# Frisbie_Board.net
KiCad netlist of a schematic drawn in EAGLE
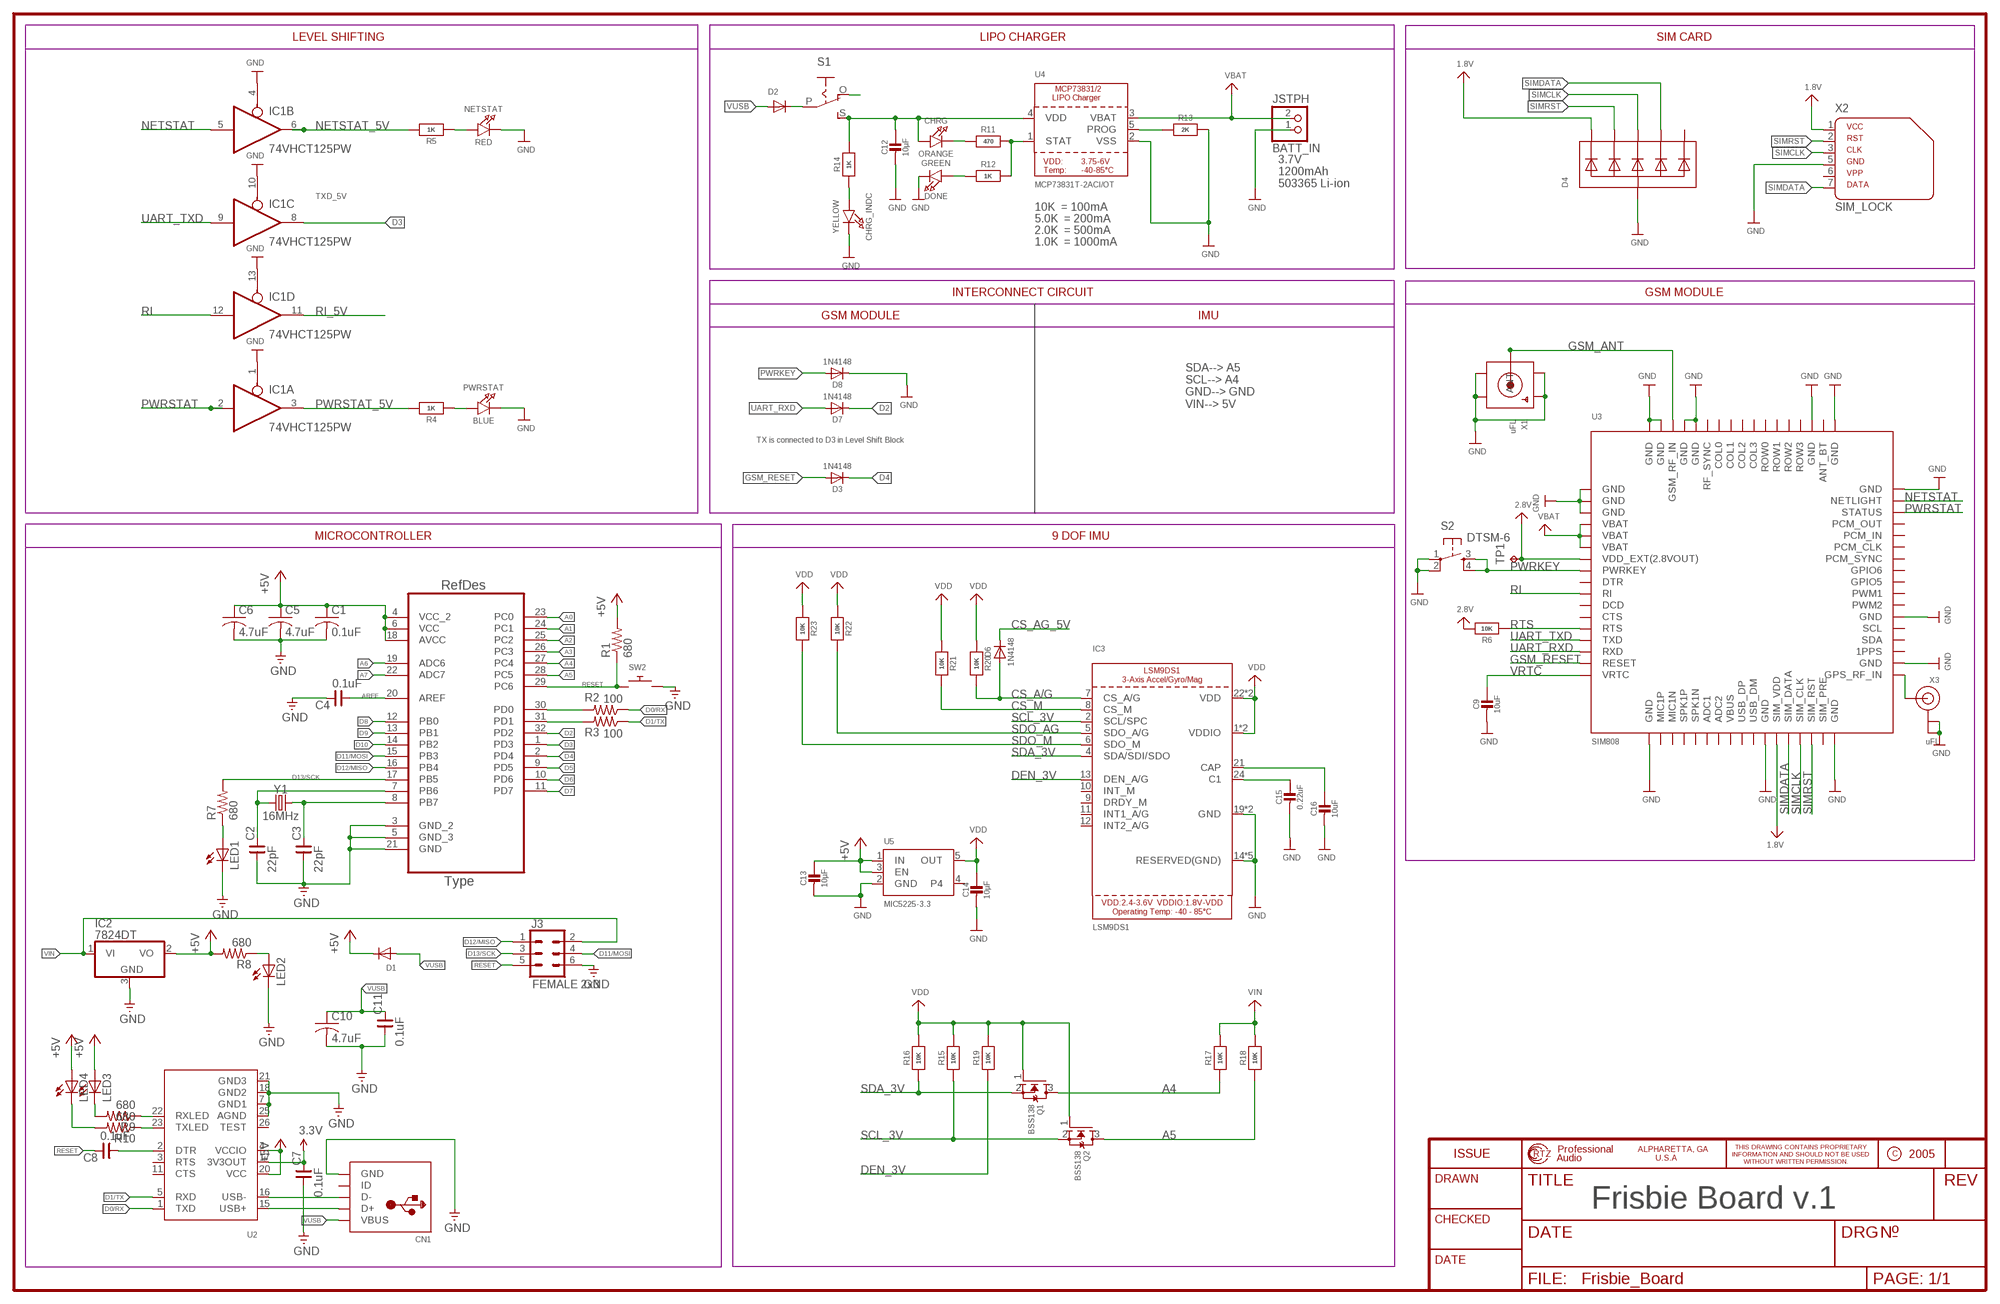
[diagram p0: schematic, sheet 1]

(export (version "E")
  (design (tool "Eeschema 10.0.6"))
  (components
    (comp (ref "BATT_IN")
      (value "JSTPH")
      (footprint "eagle-import:JSTPH2")
      (libsource (lib "eagle-import") (part "JST_2PIN"))
    )
    (comp (ref "C1")
      (value "0.1uF")
      (footprint "eagle-import:C0805")
      (libsource (lib "eagle-import") (part "C-USC0805"))
    )
    (comp (ref "C2")
      (value "22pF")
      (footprint "eagle-import:0805")
      (libsource (lib "eagle-import") (part "CNP-0805"))
    )
    (comp (ref "C3")
      (value "22pF")
      (footprint "eagle-import:0805")
      (libsource (lib "eagle-import") (part "CNP-0805"))
    )
    (comp (ref "C4")
      (value "0.1uF")
      (footprint "eagle-import:0805")
      (libsource (lib "eagle-import") (part "CNP-0805"))
    )
    (comp (ref "C5")
      (value "4.7uF")
      (footprint "eagle-import:C0805")
      (libsource (lib "eagle-import") (part "C-USC0805"))
    )
    (comp (ref "C6")
      (value "4.7uF")
      (footprint "eagle-import:C0805")
      (libsource (lib "eagle-import") (part "C-USC0805"))
    )
    (comp (ref "C7")
      (value "0.1uF")
      (footprint "eagle-import:0805")
      (libsource (lib "eagle-import") (part "CNP-0805"))
    )
    (comp (ref "C8")
      (value "0.1uF")
      (footprint "eagle-import:0805")
      (libsource (lib "eagle-import") (part "CNP-0805"))
    )
    (comp (ref "C9")
      (value "10uF")
      (footprint "eagle-import:0805-NO")
      (libsource (lib "eagle-import") (part "CAP_CERAMIC0805-NOOUTLINE"))
    )
    (comp (ref "C10")
      (value "4.7uF")
      (footprint "eagle-import:C0805")
      (libsource (lib "eagle-import") (part "C-USC0805"))
    )
    (comp (ref "C11")
      (value "0.1uF")
      (footprint "eagle-import:0805")
      (libsource (lib "eagle-import") (part "CNP-0805"))
    )
    (comp (ref "C12")
      (value "10µF")
      (footprint "eagle-import:0805-NO")
      (libsource (lib "eagle-import") (part "CAP_CERAMIC0805-NOOUTLINE"))
    )
    (comp (ref "C13")
      (value "10µF")
      (footprint "eagle-import:0805-NO")
      (libsource (lib "eagle-import") (part "CAP_CERAMIC0805-NOOUTLINE"))
    )
    (comp (ref "C14")
      (value "10µF")
      (footprint "eagle-import:0805-NO")
      (libsource (lib "eagle-import") (part "CAP_CERAMIC0805-NOOUTLINE"))
    )
    (comp (ref "C15")
      (value "0.22uF")
      (footprint "eagle-import:0805_10MGAP")
      (libsource (lib "eagle-import") (part "CAP_CERAMIC0805_10MGAP"))
    )
    (comp (ref "C16")
      (value "10uF")
      (footprint "eagle-import:0805-NO")
      (libsource (lib "eagle-import") (part "CAP_CERAMIC0805-NOOUTLINE"))
    )
    (comp (ref "CHRG")
      (value "ORANGE")
      (footprint "eagle-import:CHIPLED_0805_NOOUTLINE")
      (libsource (lib "eagle-import") (part "LED0805_NOOUTLINE"))
    )
    (comp (ref "CHRG_INDC")
      (value "YELLOW")
      (footprint "eagle-import:CHIPLED_0805_NOOUTLINE")
      (libsource (lib "eagle-import") (part "LED0805_NOOUTLINE"))
    )
    (comp (ref "CN1")
      (value "USBMINIB")
      (footprint "eagle-import:USB-MINIB")
      (libsource (lib "eagle-import") (part "USBMINIB"))
    )
    (comp (ref "D1")
      (value "DIODESOD-123")
      (footprint "eagle-import:SOD-123")
      (libsource (lib "eagle-import") (part "DIODESOD-123"))
    )
    (comp (ref "D2")
      (value "DIODESOD-123")
      (footprint "eagle-import:SOD-123")
      (libsource (lib "eagle-import") (part "DIODESOD-123"))
    )
    (comp (ref "D3")
      (value "1N4148")
      (footprint "eagle-import:SOD-323")
      (libsource (lib "eagle-import") (part "DIODESOD-323"))
    )
    (comp (ref "D4")
      (value "TVSARRAY_5LANE")
      (footprint "eagle-import:SOT363")
      (libsource (lib "eagle-import") (part "TVSARRAY_5LANE"))
    )
    (comp (ref "D6")
      (value "1N4148")
      (footprint "eagle-import:SOD-323")
      (libsource (lib "eagle-import") (part "DIODESOD-323"))
    )
    (comp (ref "D7")
      (value "1N4148")
      (footprint "eagle-import:SOD-323")
      (libsource (lib "eagle-import") (part "DIODESOD-323"))
    )
    (comp (ref "D8")
      (value "1N4148")
      (footprint "eagle-import:SOD-323")
      (libsource (lib "eagle-import") (part "DIODESOD-323"))
    )
    (comp (ref "DONE")
      (value "GREEN")
      (footprint "eagle-import:CHIPLED_0805_NOOUTLINE")
      (libsource (lib "eagle-import") (part "LED0805_NOOUTLINE"))
    )
    (comp (ref "IC1")
      (value "74VHCT125PW")
      (footprint "eagle-import:TSSOP14")
      (libsource (lib "eagle-import") (part "74125PWABT"))
    )
    (comp (ref "IC2")
      (value "7824DT")
      (footprint "eagle-import:TO252")
      (libsource (lib "eagle-import") (part "78DT24"))
    )
    (comp (ref "IC3")
      (value "LSM9DS1")
      (footprint "eagle-import:LGA24_3.5X3.1MM")
      (libsource (lib "eagle-import") (part "LSM9DS1"))
    )
    (comp (ref "J3")
      (value "FEMALE 2x3")
      (footprint "eagle-import:2X3")
      (libsource (lib "eagle-import") (part "CONN_03X2FEMALE"))
    )
    (comp (ref "LED1")
      (value "LEDCHIPLED_0805")
      (footprint "eagle-import:CHIPLED_0805")
      (libsource (lib "eagle-import") (part "LEDCHIPLED_0805"))
    )
    (comp (ref "LED2")
      (value "LEDCHIPLED_0805")
      (footprint "eagle-import:CHIPLED_0805")
      (libsource (lib "eagle-import") (part "LEDCHIPLED_0805"))
    )
    (comp (ref "LED3")
      (value "LEDCHIPLED_0805")
      (footprint "eagle-import:CHIPLED_0805")
      (libsource (lib "eagle-import") (part "LEDCHIPLED_0805"))
    )
    (comp (ref "LED4")
      (value "LEDCHIPLED_0805")
      (footprint "eagle-import:CHIPLED_0805")
      (libsource (lib "eagle-import") (part "LEDCHIPLED_0805"))
    )
    (comp (ref "NETSTAT")
      (value "RED")
      (footprint "eagle-import:CHIPLED_0805_NOOUTLINE")
      (libsource (lib "eagle-import") (part "LED0805_NOOUTLINE"))
    )
    (comp (ref "PWRSTAT")
      (value "BLUE")
      (footprint "eagle-import:CHIPLED_0805_NOOUTLINE")
      (libsource (lib "eagle-import") (part "LED0805_NOOUTLINE"))
    )
    (comp (ref "Q1")
      (value "BSS138")
      (footprint "eagle-import:SOT23-WIDE")
      (libsource (lib "eagle-import") (part "MOSFET-NWIDE"))
    )
    (comp (ref "Q2")
      (value "BSS138")
      (footprint "eagle-import:SOT23-WIDE")
      (libsource (lib "eagle-import") (part "MOSFET-NWIDE"))
    )
    (comp (ref "R1")
      (value "680")
      (footprint "eagle-import:R0805")
      (libsource (lib "eagle-import") (part "R-US_R0805"))
    )
    (comp (ref "R2")
      (value "100")
      (footprint "eagle-import:R0805")
      (libsource (lib "eagle-import") (part "R-US_R0805"))
    )
    (comp (ref "R3")
      (value "100")
      (footprint "eagle-import:R0805")
      (libsource (lib "eagle-import") (part "R-US_R0805"))
    )
    (comp (ref "R4")
      (value "1K")
      (footprint "eagle-import:0805-NO")
      (libsource (lib "eagle-import") (part "RESISTOR0805_NOOUTLINE"))
    )
    (comp (ref "R5")
      (value "1K")
      (footprint "eagle-import:0805-NO")
      (libsource (lib "eagle-import") (part "RESISTOR0805_NOOUTLINE"))
    )
    (comp (ref "R6")
      (value "10K")
      (footprint "eagle-import:0805-NO")
      (libsource (lib "eagle-import") (part "RESISTOR0805_NOOUTLINE"))
    )
    (comp (ref "R7")
      (value "680")
      (footprint "eagle-import:R0805")
      (libsource (lib "eagle-import") (part "R-US_R0805"))
    )
    (comp (ref "R8")
      (value "680")
      (footprint "eagle-import:R0805")
      (libsource (lib "eagle-import") (part "R-US_R0805"))
    )
    (comp (ref "R9")
      (value "680")
      (footprint "eagle-import:R0805")
      (libsource (lib "eagle-import") (part "R-US_R0805"))
    )
    (comp (ref "R10")
      (value "680")
      (footprint "eagle-import:R0805")
      (libsource (lib "eagle-import") (part "R-US_R0805"))
    )
    (comp (ref "R11")
      (value "470")
      (footprint "eagle-import:0805-NO")
      (libsource (lib "eagle-import") (part "RESISTOR0805_NOOUTLINE"))
    )
    (comp (ref "R12")
      (value "1K")
      (footprint "eagle-import:0805-NO")
      (libsource (lib "eagle-import") (part "RESISTOR0805_NOOUTLINE"))
    )
    (comp (ref "R13")
      (value "2K")
      (footprint "eagle-import:0805-NO")
      (libsource (lib "eagle-import") (part "RESISTOR0805_NOOUTLINE"))
    )
    (comp (ref "R14")
      (value "1K")
      (footprint "eagle-import:0805-NO")
      (libsource (lib "eagle-import") (part "RESISTOR0805_NOOUTLINE"))
    )
    (comp (ref "R15")
      (value "10K")
      (footprint "eagle-import:0805-NO")
      (libsource (lib "eagle-import") (part "RESISTOR0805_NOOUTLINE"))
    )
    (comp (ref "R16")
      (value "10K")
      (footprint "eagle-import:0805_10MGAP")
      (libsource (lib "eagle-import") (part "RESISTOR0805_10MGAP"))
    )
    (comp (ref "R17")
      (value "10K")
      (footprint "eagle-import:0805-NO")
      (libsource (lib "eagle-import") (part "RESISTOR0805_NOOUTLINE"))
    )
    (comp (ref "R18")
      (value "10K")
      (footprint "eagle-import:0805-NO")
      (libsource (lib "eagle-import") (part "RESISTOR0805_NOOUTLINE"))
    )
    (comp (ref "R19")
      (value "10K")
      (footprint "eagle-import:0805-NO")
      (libsource (lib "eagle-import") (part "RESISTOR0805_NOOUTLINE"))
    )
    (comp (ref "R20")
      (value "10K")
      (footprint "eagle-import:0805-NO")
      (libsource (lib "eagle-import") (part "RESISTOR0805_NOOUTLINE"))
    )
    (comp (ref "R21")
      (value "10K")
      (footprint "eagle-import:0805-NO")
      (libsource (lib "eagle-import") (part "RESISTOR0805_NOOUTLINE"))
    )
    (comp (ref "R22")
      (value "10K")
      (footprint "eagle-import:0805_10MGAP")
      (libsource (lib "eagle-import") (part "RESISTOR0805_10MGAP"))
    )
    (comp (ref "R23")
      (value "10K")
      (footprint "eagle-import:0805-NO")
      (libsource (lib "eagle-import") (part "RESISTOR0805_NOOUTLINE"))
    )
    (comp (ref "S1")
      (value "EG1218S")
      (footprint "eagle-import:EG1218")
      (libsource (lib "eagle-import") (part "EG1218S"))
    )
    (comp (ref "S2")
      (value "DTSM-6")
      (footprint "eagle-import:DTSM-6")
      (libsource (lib "eagle-import") (part "DTSM-6"))
    )
    (comp (ref "SW2")
      (value "SWITCH_PUSHBUTTONEVQ-PE")
      (footprint "eagle-import:TACT_PANA-EVQ")
      (libsource (lib "eagle-import") (part "SWITCH_PUSHBUTTONEVQ-PE"))
    )
    (comp (ref "TP1")
      (value "TPTP11R")
      (footprint "eagle-import:TP11R")
      (libsource (lib "eagle-import") (part "TPTP11R"))
    )
    (comp (ref "U1")
      (value "ATMEGA328P-AU")
      (footprint "eagle-import:QFP80P900X900X120-32N")
      (libsource (lib "eagle-import") (part "ATMEGA328P-AU"))
    )
    (comp (ref "U2")
      (value "FT232RLSSOP28")
      (footprint "eagle-import:SSOP28DB")
      (libsource (lib "eagle-import") (part "FT232RLSSOP28"))
    )
    (comp (ref "U3")
      (value "SIM808")
      (footprint "eagle-import:SIM900_SMT")
      (libsource (lib "eagle-import") (part "GSM_SIM808_LITERAL"))
    )
    (comp (ref "U4")
      (value "MCP73831T-2ACI/OT")
      (footprint "eagle-import:SOT23-5")
      (libsource (lib "eagle-import") (part "MCP73831/2"))
    )
    (comp (ref "U5")
      (value "MIC5225-3.3")
      (footprint "eagle-import:SOT23-5")
      (libsource (lib "eagle-import") (part "VREG_SOT23-5"))
    )
    (comp (ref "X1")
      (value "uFL")
      (footprint "eagle-import:SMA_EDGELAUNCH_UFL")
      (libsource (lib "eagle-import") (part "SMACONNECTOR_EDGE_UFL"))
    )
    (comp (ref "X2")
      (value "SIM_LOCK")
      (footprint "eagle-import:SIM_5002")
      (libsource (lib "eagle-import") (part "SIM_LOCK"))
    )
    (comp (ref "X3")
      (value "uFL")
      (footprint "eagle-import:U.FL")
      (libsource (lib "eagle-import") (part "ANTENNA_U.FL"))
    )
    (comp (ref "Y1")
      (value "16MHz")
      (footprint "eagle-import:HC49US")
      (libsource (lib "eagle-import") (part "CRYSTAL-16MHZPTH-HC49US"))
    )
  )
  (nets
    (net (code "1") (name "+5V") (class "Default")
      (node (ref "C1") (pin "1") (pinfunction "1_1") (pintype "passive"))
      (node (ref "C13") (pin "1") (pinfunction "1_1") (pintype "passive"))
      (node (ref "C5") (pin "1") (pinfunction "1_1") (pintype "passive"))
      (node (ref "C6") (pin "1") (pinfunction "1_1") (pintype "passive"))
      (node (ref "D1") (pin "C") (pinfunction "C_C") (pintype "passive"))
      (node (ref "IC2") (pin "2") (pinfunction "VO_2") (pintype "passive"))
      (node (ref "LED3") (pin "A") (pinfunction "A_A") (pintype "passive"))
      (node (ref "LED4") (pin "A") (pinfunction "A_A") (pintype "passive"))
      (node (ref "R1") (pin "2") (pinfunction "2_2") (pintype "passive"))
      (node (ref "R8") (pin "2") (pinfunction "2_2") (pintype "passive"))
      (node (ref "U1") (pin "18") (pinfunction "AVCC_18") (pintype "power_in"))
      (node (ref "U1") (pin "4") (pinfunction "VCC_2_4") (pintype "power_in"))
      (node (ref "U1") (pin "6") (pinfunction "VCC_6") (pintype "power_in"))
      (node (ref "U2") (pin "20") (pinfunction "VCC_20") (pintype "power_in"))
      (node (ref "U2") (pin "4") (pinfunction "VCCIO_4") (pintype "power_in"))
      (node (ref "U5") (pin "1") (pinfunction "IN_1") (pintype "power_in"))
      (node (ref "U5") (pin "3") (pinfunction "EN_3") (pintype "input"))
    )
    (net (code "2") (name "/AREF") (class "Default")
      (node (ref "C4") (pin "1") (pinfunction "1_1") (pintype "passive"))
      (node (ref "U1") (pin "20") (pinfunction "AREF_20") (pintype "input"))
    )
    (net (code "3") (name "/CS_AG_5V") (class "Default")
      (node (ref "D6") (pin "C") (pinfunction "C_C") (pintype "passive"))
    )
    (net (code "4") (name "/CS_A{slash}G") (class "Default")
      (node (ref "D6") (pin "A") (pinfunction "A_A") (pintype "passive"))
      (node (ref "IC3") (pin "7") (pinfunction "CS_A/G_7") (pintype "bidirectional"))
      (node (ref "R20") (pin "2") (pinfunction "2_2") (pintype "passive"))
    )
    (net (code "5") (name "/CS_M") (class "Default")
      (node (ref "IC3") (pin "8") (pinfunction "CS_M_8") (pintype "bidirectional"))
      (node (ref "R21") (pin "2") (pinfunction "2_2") (pintype "passive"))
    )
    (net (code "6") (name "/DEN_3V") (class "Default")
      (node (ref "IC3") (pin "13") (pinfunction "DEN_A/G_13") (pintype "bidirectional"))
      (node (ref "R19") (pin "1") (pinfunction "1_1") (pintype "passive"))
    )
    (net (code "7") (name "/GSM_ANT") (class "Default")
      (node (ref "U3") (pin "P$66") (pinfunction "GSM_RF_IN_P$66") (pintype "input"))
      (node (ref "X1") (pin "P") (pinfunction "ANT_P") (pintype "bidirectional"))
    )
    (net (code "8") (name "/NETSTAT") (class "Default")
      (node (ref "IC1") (pin "5") (pinfunction "I_5") (pintype "input"))
      (node (ref "U3") (pin "P$50") (pinfunction "NETLIGHT_P$50") (pintype "output"))
    )
    (net (code "9") (name "/NETSTAT_5V") (class "Default")
      (node (ref "IC1") (pin "6") (pinfunction "O_6") (pintype "tri_state"))
      (node (ref "R5") (pin "2") (pinfunction "2_2") (pintype "passive"))
    )
    (net (code "10") (name "/PWRSTAT") (class "Default")
      (node (ref "IC1") (pin "2") (pinfunction "I_2") (pintype "input"))
      (node (ref "U3") (pin "P$49") (pinfunction "STATUS_P$49") (pintype "output"))
    )
    (net (code "11") (name "/PWRSTAT_5V") (class "Default")
      (node (ref "IC1") (pin "3") (pinfunction "O_3") (pintype "tri_state"))
      (node (ref "R4") (pin "2") (pinfunction "2_2") (pintype "passive"))
    )
    (net (code "12") (name "/RI") (class "Default")
      (node (ref "IC1") (pin "12") (pinfunction "I_12") (pintype "input"))
      (node (ref "U3") (pin "P$10") (pinfunction "RI_P$10") (pintype "output"))
    )
    (net (code "13") (name "/RI_5V") (class "Default")
      (node (ref "IC1") (pin "11") (pinfunction "O_11") (pintype "tri_state"))
    )
    (net (code "14") (name "/RTS") (class "Default")
      (node (ref "R6") (pin "1") (pinfunction "1_1") (pintype "passive"))
      (node (ref "U3") (pin "P$13") (pinfunction "RTS_P$13") (pintype "input"))
    )
    (net (code "15") (name "/SCL_3V") (class "Default")
      (node (ref "IC3") (pin "2") (pinfunction "SCL/SPC_2") (pintype "bidirectional"))
      (node (ref "Q2") (pin "2") (pinfunction "S_2") (pintype "bidirectional"))
      (node (ref "R15") (pin "1") (pinfunction "1_1") (pintype "passive"))
    )
    (net (code "16") (name "/SDA_3V") (class "Default")
      (node (ref "IC3") (pin "4") (pinfunction "SDA/SDI/SDO_4") (pintype "bidirectional"))
      (node (ref "Q1") (pin "2") (pinfunction "S_2") (pintype "bidirectional"))
      (node (ref "R16") (pin "1") (pinfunction "1_1") (pintype "passive"))
    )
    (net (code "17") (name "/SDO_AG") (class "Default")
      (node (ref "IC3") (pin "5") (pinfunction "SDO_A/G_5") (pintype "bidirectional"))
      (node (ref "R22") (pin "2") (pinfunction "2_2") (pintype "passive"))
    )
    (net (code "18") (name "/SDO_M") (class "Default")
      (node (ref "IC3") (pin "6") (pinfunction "SDO_M_6") (pintype "bidirectional"))
      (node (ref "R23") (pin "2") (pinfunction "2_2") (pintype "passive"))
    )
    (net (code "19") (name "/UART_TXD") (class "Default")
      (node (ref "IC1") (pin "9") (pinfunction "I_9") (pintype "input"))
      (node (ref "U3") (pin "P$14") (pinfunction "TXD_P$14") (pintype "output"))
    )
    (net (code "20") (name "/VBUS") (class "Default")
      (node (ref "U3") (pin "P$25") (pinfunction "VBUS_P$25") (pintype "power_in"))
    )
    (net (code "21") (name "/VRTC") (class "Default")
      (node (ref "C9") (pin "1") (pinfunction "1_1") (pintype "passive"))
      (node (ref "U3") (pin "P$17") (pinfunction "VRTC_P$17") (pintype "power_in"))
    )
    (net (code "22") (name "1.8V") (class "Default")
      (node (ref "D4") (pin "1") (pinfunction "C1_1") (pintype "passive"))
      (node (ref "U3") (pin "P$29") (pinfunction "SIM_VDD_P$29") (pintype "power_in"))
      (node (ref "X2") (pin "1") (pinfunction "1_1") (pintype "passive"))
    )
    (net (code "23") (name "2.8V") (class "Default")
      (node (ref "R6") (pin "2") (pinfunction "2_2") (pintype "passive"))
      (node (ref "TP1") (pin "TP") (pinfunction "TP_TP") (pintype "input"))
      (node (ref "U3") (pin "P$7") (pinfunction "VDD_EXT(2.8VOUT)_P$7") (pintype "power_in"))
    )
    (net (code "24") (name "3.3V") (class "Default")
      (node (ref "C7") (pin "2") (pinfunction "2_2") (pintype "passive"))
      (node (ref "U2") (pin "17") (pinfunction "3V3OUT_17") (pintype "power_in"))
    )
    (net (code "25") (name "A0") (class "Default")
      (node (ref "U1") (pin "23") (pinfunction "PC0_23") (pintype "bidirectional"))
    )
    (net (code "26") (name "A1") (class "Default")
      (node (ref "U1") (pin "24") (pinfunction "PC1_24") (pintype "bidirectional"))
    )
    (net (code "27") (name "A2") (class "Default")
      (node (ref "U1") (pin "25") (pinfunction "PC2_25") (pintype "bidirectional"))
    )
    (net (code "28") (name "A3") (class "Default")
      (node (ref "U1") (pin "26") (pinfunction "PC3_26") (pintype "bidirectional"))
    )
    (net (code "29") (name "A4") (class "Default")
      (node (ref "Q1") (pin "3") (pinfunction "D_3") (pintype "bidirectional"))
      (node (ref "R17") (pin "1") (pinfunction "1_1") (pintype "passive"))
      (node (ref "U1") (pin "27") (pinfunction "PC4_27") (pintype "bidirectional"))
    )
    (net (code "30") (name "A5") (class "Default")
      (node (ref "Q2") (pin "3") (pinfunction "D_3") (pintype "bidirectional"))
      (node (ref "R18") (pin "1") (pinfunction "1_1") (pintype "passive"))
      (node (ref "U1") (pin "28") (pinfunction "PC5_28") (pintype "bidirectional"))
    )
    (net (code "31") (name "A6") (class "Default")
      (node (ref "U1") (pin "19") (pinfunction "ADC6_19") (pintype "input"))
    )
    (net (code "32") (name "A7") (class "Default")
      (node (ref "U1") (pin "22") (pinfunction "ADC7_22") (pintype "input"))
    )
    (net (code "33") (name "D0{slash}RX") (class "Default")
      (node (ref "R2") (pin "1") (pinfunction "1_1") (pintype "passive"))
      (node (ref "U2") (pin "1") (pinfunction "TXD_1") (pintype "output"))
    )
    (net (code "34") (name "D1{slash}TX") (class "Default")
      (node (ref "R3") (pin "1") (pinfunction "1_1") (pintype "passive"))
      (node (ref "U2") (pin "5") (pinfunction "RXD_5") (pintype "input"))
    )
    (net (code "35") (name "D2") (class "Default")
      (node (ref "D7") (pin "C") (pinfunction "C_C") (pintype "passive"))
      (node (ref "U1") (pin "32") (pinfunction "PD2_32") (pintype "bidirectional"))
    )
    (net (code "36") (name "D3") (class "Default")
      (node (ref "IC1") (pin "8") (pinfunction "O_8") (pintype "tri_state"))
      (node (ref "U1") (pin "1") (pinfunction "PD3_1") (pintype "bidirectional"))
    )
    (net (code "37") (name "D4") (class "Default")
      (node (ref "D3") (pin "C") (pinfunction "C_C") (pintype "passive"))
      (node (ref "U1") (pin "2") (pinfunction "PD4_2") (pintype "bidirectional"))
    )
    (net (code "38") (name "D5") (class "Default")
      (node (ref "U1") (pin "9") (pinfunction "PD5_9") (pintype "bidirectional"))
    )
    (net (code "39") (name "D6") (class "Default")
      (node (ref "U1") (pin "10") (pinfunction "PD6_10") (pintype "bidirectional"))
    )
    (net (code "40") (name "D7") (class "Default")
      (node (ref "U1") (pin "11") (pinfunction "PD7_11") (pintype "bidirectional"))
    )
    (net (code "41") (name "D8") (class "Default")
      (node (ref "U1") (pin "12") (pinfunction "PB0_12") (pintype "bidirectional"))
    )
    (net (code "42") (name "D9") (class "Default")
      (node (ref "U1") (pin "13") (pinfunction "PB1_13") (pintype "bidirectional"))
    )
    (net (code "43") (name "D10") (class "Default")
      (node (ref "U1") (pin "14") (pinfunction "PB2_14") (pintype "bidirectional"))
    )
    (net (code "44") (name "D11{slash}MOSI") (class "Default")
      (node (ref "J3") (pin "4") (pinfunction "4_4") (pintype "bidirectional"))
      (node (ref "U1") (pin "15") (pinfunction "PB3_15") (pintype "bidirectional"))
    )
    (net (code "45") (name "D12{slash}MISO") (class "Default")
      (node (ref "J3") (pin "1") (pinfunction "1_1") (pintype "bidirectional"))
      (node (ref "U1") (pin "16") (pinfunction "PB4_16") (pintype "bidirectional"))
    )
    (net (code "46") (name "D13{slash}SCK") (class "Default")
      (node (ref "J3") (pin "3") (pinfunction "3_3") (pintype "bidirectional"))
      (node (ref "R7") (pin "2") (pinfunction "2_2") (pintype "passive"))
      (node (ref "U1") (pin "17") (pinfunction "PB5_17") (pintype "bidirectional"))
    )
    (net (code "47") (name "GND") (class "Default")
      (node (ref "BATT_IN") (pin "1") (pinfunction "1_1") (pintype "passive"))
      (node (ref "C1") (pin "2") (pinfunction "2_2") (pintype "passive"))
      (node (ref "C10") (pin "2") (pinfunction "2_2") (pintype "passive"))
      (node (ref "C11") (pin "1") (pinfunction "1_1") (pintype "passive"))
      (node (ref "C12") (pin "2") (pinfunction "2_2") (pintype "passive"))
      (node (ref "C13") (pin "2") (pinfunction "2_2") (pintype "passive"))
      (node (ref "C14") (pin "2") (pinfunction "2_2") (pintype "passive"))
      (node (ref "C15") (pin "2") (pinfunction "2_2") (pintype "passive"))
      (node (ref "C16") (pin "2") (pinfunction "2_2") (pintype "passive"))
      (node (ref "C2") (pin "1") (pinfunction "1_1") (pintype "passive"))
      (node (ref "C3") (pin "1") (pinfunction "1_1") (pintype "passive"))
      (node (ref "C4") (pin "2") (pinfunction "2_2") (pintype "passive"))
      (node (ref "C5") (pin "2") (pinfunction "2_2") (pintype "passive"))
      (node (ref "C6") (pin "2") (pinfunction "2_2") (pintype "passive"))
      (node (ref "C7") (pin "1") (pinfunction "1_1") (pintype "passive"))
      (node (ref "C9") (pin "2") (pinfunction "2_2") (pintype "passive"))
      (node (ref "CHRG_INDC") (pin "C") (pinfunction "C_C") (pintype "passive"))
      (node (ref "CN1") (pin "GND") (pinfunction "GND_GND") (pintype "power_in"))
      (node (ref "D4") (pin "2") (pinfunction "A_2") (pintype "passive"))
      (node (ref "D8") (pin "C") (pinfunction "C_C") (pintype "passive"))
      (node (ref "DONE") (pin "C") (pinfunction "C_C") (pintype "passive"))
      (node (ref "IC1") (pin "1") (pinfunction "OE_1") (pintype "input"))
      (node (ref "IC1") (pin "10") (pinfunction "OE_10") (pintype "input"))
      (node (ref "IC1") (pin "13") (pinfunction "OE_13") (pintype "input"))
      (node (ref "IC1") (pin "4") (pinfunction "OE_4") (pintype "input"))
      (node (ref "IC2") (pin "3") (pinfunction "GND_3") (pintype "passive"))
      (node (ref "IC3") (pin "14") (pinfunction "RESERVED(GND)_14") (pintype "power_in"))
      (node (ref "IC3") (pin "15") (pinfunction "RESERVED(GND)_15") (pintype "power_in"))
      (node (ref "IC3") (pin "16") (pinfunction "RESERVED(GND)_16") (pintype "power_in"))
      (node (ref "IC3") (pin "17") (pinfunction "RESERVED(GND)_17") (pintype "power_in"))
      (node (ref "IC3") (pin "18") (pinfunction "RESERVED(GND)_18") (pintype "power_in"))
      (node (ref "IC3") (pin "19") (pinfunction "GND_19") (pintype "power_in"))
      (node (ref "IC3") (pin "20") (pinfunction "GND_20") (pintype "power_in"))
      (node (ref "J3") (pin "6") (pinfunction "6_6") (pintype "bidirectional"))
      (node (ref "LED1") (pin "C") (pinfunction "C_C") (pintype "passive"))
      (node (ref "LED2") (pin "C") (pinfunction "C_C") (pintype "passive"))
      (node (ref "NETSTAT") (pin "C") (pinfunction "C_C") (pintype "passive"))
      (node (ref "PWRSTAT") (pin "C") (pinfunction "C_C") (pintype "passive"))
      (node (ref "R13") (pin "2") (pinfunction "2_2") (pintype "passive"))
      (node (ref "S2") (pin "1") (pinfunction "1_1") (pintype "passive"))
      (node (ref "S2") (pin "2") (pinfunction "2_2") (pintype "passive"))
      (node (ref "SW2") (pin "P$2") (pinfunction "P$2_P$2") (pintype "passive"))
      (node (ref "U1") (pin "21") (pinfunction "GND_21") (pintype "passive"))
      (node (ref "U1") (pin "3") (pinfunction "GND_2_3") (pintype "passive"))
      (node (ref "U1") (pin "5") (pinfunction "GND_3_5") (pintype "passive"))
      (node (ref "U2") (pin "18") (pinfunction "GND2_18") (pintype "power_in"))
      (node (ref "U2") (pin "21") (pinfunction "GND3_21") (pintype "power_in"))
      (node (ref "U2") (pin "25") (pinfunction "AGND_25") (pintype "power_in"))
      (node (ref "U2") (pin "7") (pinfunction "GND1_7") (pintype "power_in"))
      (node (ref "U3") (pin "P$1") (pinfunction "GND_P$1") (pintype "power_in"))
      (node (ref "U3") (pin "P$18") (pinfunction "GND_P$18") (pintype "power_in"))
      (node (ref "U3") (pin "P$2") (pinfunction "GND_P$2") (pintype "power_in"))
      (node (ref "U3") (pin "P$28") (pinfunction "GND_P$28") (pintype "power_in"))
      (node (ref "U3") (pin "P$3") (pinfunction "GND_P$3") (pintype "power_in"))
      (node (ref "U3") (pin "P$34") (pinfunction "GND_P$34") (pintype "power_in"))
      (node (ref "U3") (pin "P$36") (pinfunction "GND_P$36") (pintype "power_in"))
      (node (ref "U3") (pin "P$40") (pinfunction "GND_P$40") (pintype "power_in"))
      (node (ref "U3") (pin "P$51") (pinfunction "GND_P$51") (pintype "power_in"))
      (node (ref "U3") (pin "P$52") (pinfunction "GND_P$52") (pintype "power_in"))
      (node (ref "U3") (pin "P$54") (pinfunction "GND_P$54") (pintype "power_in"))
      (node (ref "U3") (pin "P$64") (pinfunction "GND_P$64") (pintype "power_in"))
      (node (ref "U3") (pin "P$65") (pinfunction "GND_P$65") (pintype "power_in"))
      (node (ref "U3") (pin "P$67") (pinfunction "GND_P$67") (pintype "power_in"))
      (node (ref "U3") (pin "P$68") (pinfunction "GND_P$68") (pintype "power_in"))
      (node (ref "U4") (pin "2") (pinfunction "VSS_2") (pintype "power_in"))
      (node (ref "U5") (pin "2") (pinfunction "GND_2") (pintype "power_in"))
      (node (ref "X1") (pin "GND@1") (pinfunction "GND1_GND@1") (pintype "power_in"))
      (node (ref "X1") (pin "GND@2") (pinfunction "GND2_GND@2") (pintype "power_in"))
      (node (ref "X1") (pin "GND@3") (pinfunction "GND3_GND@3") (pintype "power_in"))
      (node (ref "X1") (pin "GND@4") (pinfunction "GND4_GND@4") (pintype "power_in"))
      (node (ref "X2") (pin "5") (pinfunction "4_5") (pintype "passive"))
      (node (ref "X3") (pin "1") (pinfunction "GND_1") (pintype "passive"))
      (node (ref "X3") (pin "2") (pinfunction "GND_2") (pintype "passive"))
    )
    (net (code "48") (name "GSM_RESET") (class "Default")
      (node (ref "D3") (pin "A") (pinfunction "A_A") (pintype "passive"))
      (node (ref "U3") (pin "P$16") (pinfunction "RESET_P$16") (pintype "input"))
    )
    (net (code "49") (name "Net-(CHRG-PadC)") (class "Default")
      (node (ref "CHRG") (pin "C") (pinfunction "C_C") (pintype "passive"))
      (node (ref "R11") (pin "1") (pinfunction "1_1") (pintype "passive"))
    )
    (net (code "50") (name "Net-(CHRG_INDC-PadA)") (class "Default")
      (node (ref "CHRG_INDC") (pin "A") (pinfunction "A_A") (pintype "passive"))
      (node (ref "R14") (pin "1") (pinfunction "1_1") (pintype "passive"))
    )
    (net (code "51") (name "Net-(D2-PadC)") (class "Default")
      (node (ref "D2") (pin "C") (pinfunction "C_C") (pintype "passive"))
      (node (ref "S1") (pin "P") (pinfunction "P_P") (pintype "passive"))
    )
    (net (code "52") (name "Net-(DONE-PadA)") (class "Default")
      (node (ref "DONE") (pin "A") (pinfunction "A_A") (pintype "passive"))
      (node (ref "R12") (pin "1") (pinfunction "1_1") (pintype "passive"))
    )
    (net (code "53") (name "Net-(IC3-C1)") (class "Default")
      (node (ref "C15") (pin "1") (pinfunction "1_1") (pintype "passive"))
      (node (ref "IC3") (pin "24") (pinfunction "C1_24") (pintype "bidirectional"))
    )
    (net (code "54") (name "Net-(IC3-CAP)") (class "Default")
      (node (ref "C16") (pin "1") (pinfunction "1_1") (pintype "passive"))
      (node (ref "IC3") (pin "21") (pinfunction "CAP_21") (pintype "bidirectional"))
    )
    (net (code "55") (name "Net-(LED1-PadA)") (class "Default")
      (node (ref "LED1") (pin "A") (pinfunction "A_A") (pintype "passive"))
      (node (ref "R7") (pin "1") (pinfunction "1_1") (pintype "passive"))
    )
    (net (code "56") (name "Net-(LED2-PadA)") (class "Default")
      (node (ref "LED2") (pin "A") (pinfunction "A_A") (pintype "passive"))
      (node (ref "R8") (pin "1") (pinfunction "1_1") (pintype "passive"))
    )
    (net (code "57") (name "Net-(LED3-PadC)") (class "Default")
      (node (ref "LED3") (pin "C") (pinfunction "C_C") (pintype "passive"))
      (node (ref "R9") (pin "2") (pinfunction "2_2") (pintype "passive"))
    )
    (net (code "58") (name "Net-(LED4-PadC)") (class "Default")
      (node (ref "LED4") (pin "C") (pinfunction "C_C") (pintype "passive"))
      (node (ref "R10") (pin "2") (pinfunction "2_2") (pintype "passive"))
    )
    (net (code "59") (name "Net-(NETSTAT-PadA)") (class "Default")
      (node (ref "NETSTAT") (pin "A") (pinfunction "A_A") (pintype "passive"))
      (node (ref "R5") (pin "1") (pinfunction "1_1") (pintype "passive"))
    )
    (net (code "60") (name "Net-(PWRSTAT-PadA)") (class "Default")
      (node (ref "PWRSTAT") (pin "A") (pinfunction "A_A") (pintype "passive"))
      (node (ref "R4") (pin "1") (pinfunction "1_1") (pintype "passive"))
    )
    (net (code "61") (name "Net-(U1-PB6)") (class "Default")
      (node (ref "C2") (pin "2") (pinfunction "2_2") (pintype "passive"))
      (node (ref "U1") (pin "7") (pinfunction "PB6_7") (pintype "bidirectional"))
      (node (ref "Y1") (pin "1") (pinfunction "1_1") (pintype "passive"))
    )
    (net (code "62") (name "Net-(U1-PB7)") (class "Default")
      (node (ref "C3") (pin "2") (pinfunction "2_2") (pintype "passive"))
      (node (ref "U1") (pin "8") (pinfunction "PB7_8") (pintype "bidirectional"))
      (node (ref "Y1") (pin "2") (pinfunction "2_2") (pintype "passive"))
    )
    (net (code "63") (name "Net-(U1-PD0)") (class "Default")
      (node (ref "R2") (pin "2") (pinfunction "2_2") (pintype "passive"))
      (node (ref "U1") (pin "30") (pinfunction "PD0_30") (pintype "bidirectional"))
    )
    (net (code "64") (name "Net-(U1-PD1)") (class "Default")
      (node (ref "R3") (pin "2") (pinfunction "2_2") (pintype "passive"))
      (node (ref "U1") (pin "31") (pinfunction "PD1_31") (pintype "bidirectional"))
    )
    (net (code "65") (name "Net-(U2-DTR)") (class "Default")
      (node (ref "C8") (pin "1") (pinfunction "1_1") (pintype "passive"))
      (node (ref "U2") (pin "2") (pinfunction "DTR_2") (pintype "bidirectional"))
    )
    (net (code "66") (name "Net-(U2-RXLED)") (class "Default")
      (node (ref "R9") (pin "1") (pinfunction "1_1") (pintype "passive"))
      (node (ref "U2") (pin "22") (pinfunction "RXLED_22") (pintype "bidirectional"))
    )
    (net (code "67") (name "Net-(U2-TXLED)") (class "Default")
      (node (ref "R10") (pin "1") (pinfunction "1_1") (pintype "passive"))
      (node (ref "U2") (pin "23") (pinfunction "TXLED_23") (pintype "bidirectional"))
    )
    (net (code "68") (name "Net-(U2-USB+)") (class "Default")
      (node (ref "CN1") (pin "D+") (pinfunction "D+_D+") (pintype "bidirectional"))
      (node (ref "U2") (pin "15") (pinfunction "USB+_15") (pintype "bidirectional"))
    )
    (net (code "69") (name "Net-(U2-USB-)") (class "Default")
      (node (ref "CN1") (pin "D-") (pinfunction "D-_D-") (pintype "bidirectional"))
      (node (ref "U2") (pin "16") (pinfunction "USB-_16") (pintype "bidirectional"))
    )
    (net (code "70") (name "Net-(U3-GPS_RF_IN)") (class "Default")
      (node (ref "U3") (pin "P$35") (pinfunction "GPS_RF_IN_P$35") (pintype "bidirectional"))
      (node (ref "X3") (pin "3") (pinfunction "SIGNAL_3") (pintype "passive"))
    )
    (net (code "71") (name "Net-(U4-PROG)") (class "Default")
      (node (ref "R13") (pin "1") (pinfunction "1_1") (pintype "passive"))
      (node (ref "U4") (pin "5") (pinfunction "PROG_5") (pintype "input"))
    )
    (net (code "72") (name "Net-(U4-STAT)") (class "Default")
      (node (ref "R11") (pin "2") (pinfunction "2_2") (pintype "passive"))
      (node (ref "R12") (pin "2") (pinfunction "2_2") (pintype "passive"))
      (node (ref "U4") (pin "1") (pinfunction "STAT_1") (pintype "output"))
    )
    (net (code "73") (name "Net-(U4-VDD)") (class "Default")
      (node (ref "C12") (pin "1") (pinfunction "1_1") (pintype "passive"))
      (node (ref "CHRG") (pin "A") (pinfunction "A_A") (pintype "passive"))
      (node (ref "R14") (pin "2") (pinfunction "2_2") (pintype "passive"))
      (node (ref "S1") (pin "S") (pinfunction "S_S") (pintype "passive"))
      (node (ref "U4") (pin "4") (pinfunction "VDD_4") (pintype "power_in"))
    )
    (net (code "74") (name "PWRKEY") (class "Default")
      (node (ref "D8") (pin "A") (pinfunction "A_A") (pintype "passive"))
      (node (ref "S2") (pin "3") (pinfunction "3_3") (pintype "passive"))
      (node (ref "S2") (pin "4") (pinfunction "4_4") (pintype "passive"))
      (node (ref "U3") (pin "P$8") (pinfunction "PWRKEY_P$8") (pintype "input"))
    )
    (net (code "75") (name "RESET") (class "Default")
      (node (ref "C8") (pin "2") (pinfunction "2_2") (pintype "passive"))
      (node (ref "J3") (pin "5") (pinfunction "5_5") (pintype "bidirectional"))
      (node (ref "R1") (pin "1") (pinfunction "1_1") (pintype "passive"))
      (node (ref "SW2") (pin "P$1") (pinfunction "P$1_P$1") (pintype "passive"))
      (node (ref "U1") (pin "29") (pinfunction "PC6_29") (pintype "bidirectional"))
    )
    (net (code "76") (name "SIMCLK") (class "Default")
      (node (ref "D4") (pin "4") (pinfunction "C3_4") (pintype "passive"))
      (node (ref "U3") (pin "P$31") (pinfunction "SIM_CLK_P$31") (pintype "output"))
      (node (ref "X2") (pin "3") (pinfunction "3_3") (pintype "passive"))
    )
    (net (code "77") (name "SIMDATA") (class "Default")
      (node (ref "D4") (pin "5") (pinfunction "C4_5") (pintype "passive"))
      (node (ref "U3") (pin "P$30") (pinfunction "SIM_DATA_P$30") (pintype "bidirectional"))
      (node (ref "X2") (pin "7") (pinfunction "6_7") (pintype "passive"))
    )
    (net (code "78") (name "SIMRST") (class "Default")
      (node (ref "D4") (pin "3") (pinfunction "C2_3") (pintype "passive"))
      (node (ref "U3") (pin "P$32") (pinfunction "SIM_RST_P$32") (pintype "output"))
      (node (ref "X2") (pin "2") (pinfunction "2_2") (pintype "passive"))
    )
    (net (code "79") (name "UART_RXD") (class "Default")
      (node (ref "D7") (pin "A") (pinfunction "A_A") (pintype "passive"))
      (node (ref "U3") (pin "P$15") (pinfunction "RXD_P$15") (pintype "input"))
    )
    (net (code "80") (name "VBAT") (class "Default")
      (node (ref "BATT_IN") (pin "2") (pinfunction "2_2") (pintype "passive"))
      (node (ref "U3") (pin "P$4") (pinfunction "VBAT_P$4") (pintype "power_in"))
      (node (ref "U3") (pin "P$5") (pinfunction "VBAT_P$5") (pintype "power_in"))
      (node (ref "U3") (pin "P$6") (pinfunction "VBAT_P$6") (pintype "power_in"))
      (node (ref "U4") (pin "3") (pinfunction "VBAT_3") (pintype "power_in"))
    )
    (net (code "81") (name "VDD") (class "Default")
      (node (ref "C14") (pin "1") (pinfunction "1_1") (pintype "passive"))
      (node (ref "IC3") (pin "1") (pinfunction "VDDIO_1") (pintype "power_in"))
      (node (ref "IC3") (pin "22") (pinfunction "VDD_22") (pintype "power_in"))
      (node (ref "IC3") (pin "23") (pinfunction "VDD_23") (pintype "power_in"))
      (node (ref "IC3") (pin "3") (pinfunction "VDDIO_3") (pintype "power_in"))
      (node (ref "Q1") (pin "1") (pinfunction "G_1") (pintype "bidirectional"))
      (node (ref "Q2") (pin "1") (pinfunction "G_1") (pintype "bidirectional"))
      (node (ref "R15") (pin "2") (pinfunction "2_2") (pintype "passive"))
      (node (ref "R16") (pin "2") (pinfunction "2_2") (pintype "passive"))
      (node (ref "R19") (pin "2") (pinfunction "2_2") (pintype "passive"))
      (node (ref "R20") (pin "1") (pinfunction "1_1") (pintype "passive"))
      (node (ref "R21") (pin "1") (pinfunction "1_1") (pintype "passive"))
      (node (ref "R22") (pin "1") (pinfunction "1_1") (pintype "passive"))
      (node (ref "R23") (pin "1") (pinfunction "1_1") (pintype "passive"))
      (node (ref "U5") (pin "5") (pinfunction "OUT_5") (pintype "power_in"))
    )
    (net (code "82") (name "VIN") (class "Default")
      (node (ref "IC2") (pin "1") (pinfunction "VI_1") (pintype "input"))
      (node (ref "J3") (pin "2") (pinfunction "2_2") (pintype "bidirectional"))
      (node (ref "R17") (pin "2") (pinfunction "2_2") (pintype "passive"))
      (node (ref "R18") (pin "2") (pinfunction "2_2") (pintype "passive"))
    )
    (net (code "83") (name "VUSB") (class "Default")
      (node (ref "C10") (pin "1") (pinfunction "1_1") (pintype "passive"))
      (node (ref "C11") (pin "2") (pinfunction "2_2") (pintype "passive"))
      (node (ref "CN1") (pin "VBUS") (pinfunction "VBUS_VBUS") (pintype "power_in"))
      (node (ref "D1") (pin "A") (pinfunction "A_A") (pintype "passive"))
      (node (ref "D2") (pin "A") (pinfunction "A_A") (pintype "passive"))
    )
    (net (code "84") (name "unconnected-(CN1-PadID)") (class "Default")
      (node (ref "CN1") (pin "ID") (pinfunction "ID_ID") (pintype "bidirectional"))
    )
    (net (code "85") (name "unconnected-(D4-C5-Pad6)") (class "Default")
      (node (ref "D4") (pin "6") (pinfunction "C5_6") (pintype "passive"))
    )
    (net (code "86") (name "unconnected-(IC3-DRDY_M-Pad9)") (class "Default")
      (node (ref "IC3") (pin "9") (pinfunction "DRDY_M_9") (pintype "bidirectional"))
    )
    (net (code "87") (name "unconnected-(IC3-INT1_A{slash}G-Pad11)") (class "Default")
      (node (ref "IC3") (pin "11") (pinfunction "INT1_A/G_11") (pintype "bidirectional"))
    )
    (net (code "88") (name "unconnected-(IC3-INT2_A{slash}G-Pad12)") (class "Default")
      (node (ref "IC3") (pin "12") (pinfunction "INT2_A/G_12") (pintype "bidirectional"))
    )
    (net (code "89") (name "unconnected-(IC3-INT_M-Pad10)") (class "Default")
      (node (ref "IC3") (pin "10") (pinfunction "INT_M_10") (pintype "bidirectional"))
    )
    (net (code "90") (name "unconnected-(S1-PadO)") (class "Default")
      (node (ref "S1") (pin "O") (pinfunction "O_O") (pintype "passive"))
    )
    (net (code "91") (name "unconnected-(U2-CTS-Pad11)") (class "Default")
      (node (ref "U2") (pin "11") (pinfunction "CTS_11") (pintype "bidirectional"))
    )
    (net (code "92") (name "unconnected-(U2-RTS-Pad3)") (class "Default")
      (node (ref "U2") (pin "3") (pinfunction "RTS_3") (pintype "bidirectional"))
    )
    (net (code "93") (name "unconnected-(U2-TEST-Pad26)") (class "Default")
      (node (ref "U2") (pin "26") (pinfunction "TEST_26") (pintype "input"))
    )
    (net (code "94") (name "unconnected-(U3-1PPS-PadP$37)") (class "Default")
      (node (ref "U3") (pin "P$37") (pinfunction "1PPS_P$37") (pintype "input"))
    )
    (net (code "95") (name "unconnected-(U3-ADC1-PadP$23)") (class "Default")
      (node (ref "U3") (pin "P$23") (pinfunction "ADC1_P$23") (pintype "input"))
    )
    (net (code "96") (name "unconnected-(U3-ADC2-PadP$24)") (class "Default")
      (node (ref "U3") (pin "P$24") (pinfunction "ADC2_P$24") (pintype "input"))
    )
    (net (code "97") (name "unconnected-(U3-ANT_BT-PadP$53)") (class "Default")
      (node (ref "U3") (pin "P$53") (pinfunction "ANT_BT_P$53") (pintype "bidirectional"))
    )
    (net (code "98") (name "unconnected-(U3-COL0-PadP$62)") (class "Default")
      (node (ref "U3") (pin "P$62") (pinfunction "COL0_P$62") (pintype "input"))
    )
    (net (code "99") (name "unconnected-(U3-COL1-PadP$61)") (class "Default")
      (node (ref "U3") (pin "P$61") (pinfunction "COL1_P$61") (pintype "input"))
    )
    (net (code "100") (name "unconnected-(U3-COL2-PadP$60)") (class "Default")
      (node (ref "U3") (pin "P$60") (pinfunction "COL2_P$60") (pintype "input"))
    )
    (net (code "101") (name "unconnected-(U3-COL3-PadP$59)") (class "Default")
      (node (ref "U3") (pin "P$59") (pinfunction "COL3_P$59") (pintype "input"))
    )
    (net (code "102") (name "unconnected-(U3-CTS-PadP$12)") (class "Default")
      (node (ref "U3") (pin "P$12") (pinfunction "CTS_P$12") (pintype "output"))
    )
    (net (code "103") (name "unconnected-(U3-DCD-PadP$11)") (class "Default")
      (node (ref "U3") (pin "P$11") (pinfunction "DCD_P$11") (pintype "output"))
    )
    (net (code "104") (name "unconnected-(U3-DTR-PadP$9)") (class "Default")
      (node (ref "U3") (pin "P$9") (pinfunction "DTR_P$9") (pintype "input"))
    )
    (net (code "105") (name "unconnected-(U3-GPIO5-PadP$43)") (class "Default")
      (node (ref "U3") (pin "P$43") (pinfunction "GPIO5_P$43") (pintype "bidirectional"))
    )
    (net (code "106") (name "unconnected-(U3-GPIO6-PadP$44)") (class "Default")
      (node (ref "U3") (pin "P$44") (pinfunction "GPIO6_P$44") (pintype "bidirectional"))
    )
    (net (code "107") (name "unconnected-(U3-MIC1N-PadP$20)") (class "Default")
      (node (ref "U3") (pin "P$20") (pinfunction "MIC1N_P$20") (pintype "input"))
    )
    (net (code "108") (name "unconnected-(U3-MIC1P-PadP$19)") (class "Default")
      (node (ref "U3") (pin "P$19") (pinfunction "MIC1P_P$19") (pintype "input"))
    )
    (net (code "109") (name "unconnected-(U3-PCM_CLK-PadP$46)") (class "Default")
      (node (ref "U3") (pin "P$46") (pinfunction "PCM_CLK_P$46") (pintype "input"))
    )
    (net (code "110") (name "unconnected-(U3-PCM_IN-PadP$47)") (class "Default")
      (node (ref "U3") (pin "P$47") (pinfunction "PCM_IN_P$47") (pintype "input"))
    )
    (net (code "111") (name "unconnected-(U3-PCM_OUT-PadP$48)") (class "Default")
      (node (ref "U3") (pin "P$48") (pinfunction "PCM_OUT_P$48") (pintype "output"))
    )
    (net (code "112") (name "unconnected-(U3-PCM_SYNC-PadP$45)") (class "Default")
      (node (ref "U3") (pin "P$45") (pinfunction "PCM_SYNC_P$45") (pintype "output"))
    )
    (net (code "113") (name "unconnected-(U3-PWM1-PadP$42)") (class "Default")
      (node (ref "U3") (pin "P$42") (pinfunction "PWM1_P$42") (pintype "output"))
    )
    (net (code "114") (name "unconnected-(U3-PWM2-PadP$41)") (class "Default")
      (node (ref "U3") (pin "P$41") (pinfunction "PWM2_P$41") (pintype "output"))
    )
    (net (code "115") (name "unconnected-(U3-RF_SYNC-PadP$63)") (class "Default")
      (node (ref "U3") (pin "P$63") (pinfunction "RF_SYNC_P$63") (pintype "output"))
    )
    (net (code "116") (name "unconnected-(U3-ROW0-PadP$58)") (class "Default")
      (node (ref "U3") (pin "P$58") (pinfunction "ROW0_P$58") (pintype "output"))
    )
    (net (code "117") (name "unconnected-(U3-ROW1-PadP$57)") (class "Default")
      (node (ref "U3") (pin "P$57") (pinfunction "ROW1_P$57") (pintype "output"))
    )
    (net (code "118") (name "unconnected-(U3-ROW2-PadP$56)") (class "Default")
      (node (ref "U3") (pin "P$56") (pinfunction "ROW2_P$56") (pintype "output"))
    )
    (net (code "119") (name "unconnected-(U3-ROW3-PadP$55)") (class "Default")
      (node (ref "U3") (pin "P$55") (pinfunction "ROW3_P$55") (pintype "output"))
    )
    (net (code "120") (name "unconnected-(U3-SCL-PadP$39)") (class "Default")
      (node (ref "U3") (pin "P$39") (pinfunction "SCL_P$39") (pintype "output"))
    )
    (net (code "121") (name "unconnected-(U3-SDA-PadP$38)") (class "Default")
      (node (ref "U3") (pin "P$38") (pinfunction "SDA_P$38") (pintype "bidirectional"))
    )
    (net (code "122") (name "unconnected-(U3-SIM_PRE-PadP$33)") (class "Default")
      (node (ref "U3") (pin "P$33") (pinfunction "SIM_PRE_P$33") (pintype "input"))
    )
    (net (code "123") (name "unconnected-(U3-SPK1N-PadP$22)") (class "Default")
      (node (ref "U3") (pin "P$22") (pinfunction "SPK1N_P$22") (pintype "output"))
    )
    (net (code "124") (name "unconnected-(U3-SPK1P-PadP$21)") (class "Default")
      (node (ref "U3") (pin "P$21") (pinfunction "SPK1P_P$21") (pintype "output"))
    )
    (net (code "125") (name "unconnected-(U3-USB_DM-PadP$27)") (class "Default")
      (node (ref "U3") (pin "P$27") (pinfunction "USB_DM_P$27") (pintype "bidirectional"))
    )
    (net (code "126") (name "unconnected-(U3-USB_DP-PadP$26)") (class "Default")
      (node (ref "U3") (pin "P$26") (pinfunction "USB_DP_P$26") (pintype "bidirectional"))
    )
    (net (code "127") (name "unconnected-(U5-P4-Pad4)") (class "Default")
      (node (ref "U5") (pin "4") (pinfunction "P4_4") (pintype "bidirectional"))
    )
    (net (code "128") (name "unconnected-(X2-5-Pad6)") (class "Default")
      (node (ref "X2") (pin "6") (pinfunction "5_6") (pintype "passive"))
    )
  )
)
